# PowerSupply.net
KiCad netlist of a schematic drawn in Altium Designer
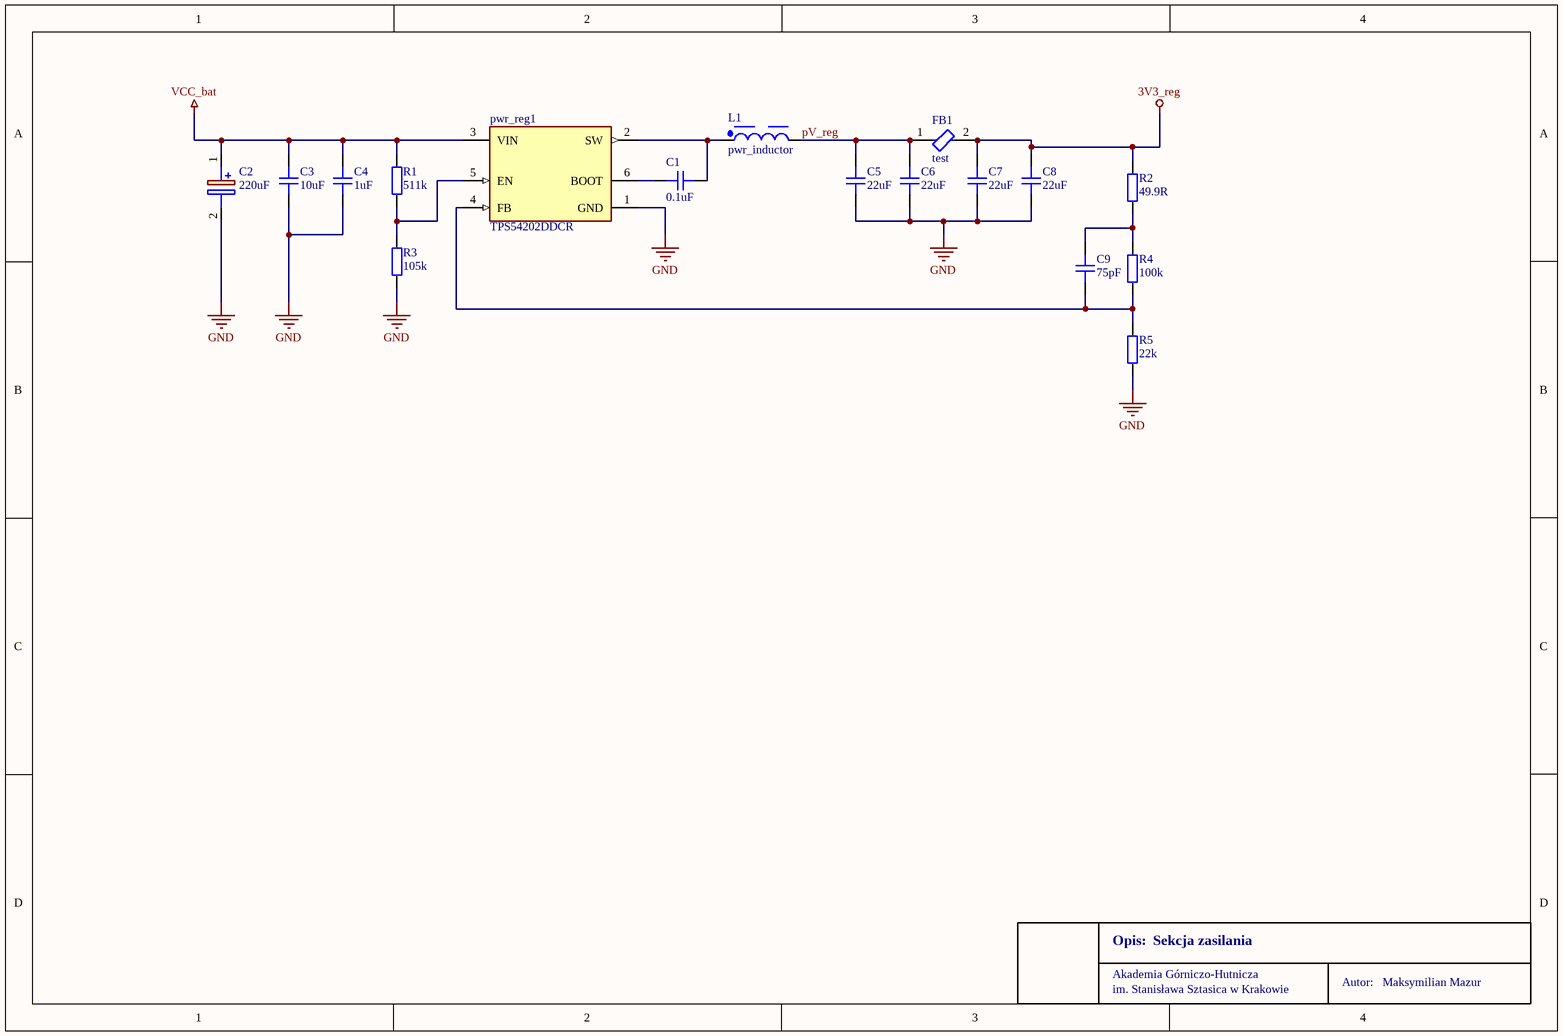
[diagram p0: PowerSupply.SchDoc]

(export (version "E")
  (design (tool "Eeschema 10.0.6"))
  (components
    (comp (ref "C1")
      (value "0.1uF")
      (footprint "CAP_0603")
      (description "Capacitor SMD 0603\r\nX7R\r\nLOW ESR")
      (libsource (lib "Schematic-Lib-PhilsLab") (part "CAP_0603"))
    )
    (comp (ref "C2")
      (value "220uF")
      (footprint "SamacSys:CAPAE660X810N")
      (description "Cap 16V 220uF\r\n\r\nInput current decap")
      (fields (field (name "MANUFACTURER_PART_NUMBER") "SC1C227M6L07KVR"))
      (libsource (lib "*") (part "SC1C227M6L07KVR"))
    )
    (comp (ref "C3")
      (value "10uF")
      (footprint "CAP_1206")
      (description "Capacitor SMD 1206\r\n25V")
      (libsource (lib "Schematic-Lib-PhilsLab") (part "CAP_1206"))
    )
    (comp (ref "C4")
      (value "1uF")
      (footprint "CAP_0603")
      (description "Capacitor SMD 0603\r\n25V")
      (libsource (lib "Schematic-Lib-PhilsLab") (part "CAP_0603"))
    )
    (comp (ref "C5")
      (value "22uF")
      (footprint "CAP_0603")
      (description "Capacitor SMD 0603\r\nX7R\r\nLOW ESR")
      (libsource (lib "Schematic-Lib-PhilsLab") (part "CAP_0603"))
    )
    (comp (ref "C6")
      (value "22uF")
      (footprint "CAP_0603")
      (description "Capacitor SMD 0603\r\nX7R\r\nLOW ESR")
      (libsource (lib "Schematic-Lib-PhilsLab") (part "CAP_0603"))
    )
    (comp (ref "C7")
      (value "22uF")
      (footprint "CAP_0603")
      (description "Capacitor SMD 0603\r\nX7R\r\nLOW ESR")
      (libsource (lib "Schematic-Lib-PhilsLab") (part "CAP_0603"))
    )
    (comp (ref "C8")
      (value "22uF")
      (footprint "CAP_0603")
      (description "Capacitor SMD 0603\r\nX7R\r\nLOW ESR")
      (libsource (lib "Schematic-Lib-PhilsLab") (part "CAP_0603"))
    )
    (comp (ref "C9")
      (value "75pF")
      (footprint "CAP_0603")
      (description "Capacitor SMD 0603")
      (libsource (lib "Schematic-Lib-PhilsLab") (part "CAP_0603"))
    )
    (comp (ref "FB1")
      (value "test")
      (footprint "FP-BLM18-0_15-t0_8-IPC_A")
      (description "Chip Ferrite Bead, 0603\r\n\r\nFor testing purpose")
      (fields (field (name "TOLERANCE") "25%"))
      (libsource (lib "Altium Content Vault") (part "5f30dd21d616792df468990f7003faa"))
    )
    (comp (ref "L1")
      (value "pwr_inductor")
      (footprint "WE-PD_7345")
      (description "15uF, 2.7A  HPI0630-150")
      (fields (field (name "TOLERANCE") "20%"))
      (libsource (lib "Altium Content Vault") (part "Inductor - 2"))
    )
    (comp (ref "pwr_reg1")
      (value "TPS54202DDCR")
      (footprint "FP-DDC0006A-IPC_B")
      (description "IC REG BUCK ADJ 2A TSOT23-6")
      (libsource (lib "Altium Content Vault") (part "35c2d3f1afc239a386b2ba50eead654"))
    )
    (comp (ref "R1")
      (value "511k")
      (footprint "RES_0603")
      (description "Resistor SMD 0603")
      (libsource (lib "Schematic-Lib-PhilsLab") (part "RES_0603"))
    )
    (comp (ref "R2")
      (value "49.9R")
      (footprint "RES_0603")
      (description "Resistor SMD 0603")
      (libsource (lib "Schematic-Lib-PhilsLab") (part "RES_0603"))
    )
    (comp (ref "R3")
      (value "105k")
      (footprint "RES_0603")
      (description "Resistor SMD 0603")
      (libsource (lib "Schematic-Lib-PhilsLab") (part "RES_0603"))
    )
    (comp (ref "R4")
      (value "100k")
      (footprint "RES_0603")
      (description "Resistor SMD 0603\r\nTolerance 1%")
      (libsource (lib "Schematic-Lib-PhilsLab") (part "RES_0603"))
    )
    (comp (ref "R5")
      (value "22k")
      (footprint "RES_0603")
      (description "Resistor SMD 0603\r\nTolerance 1%")
      (libsource (lib "Schematic-Lib-PhilsLab") (part "RES_0603"))
    )
  )
  (nets
    (net (code "1") (name "/pV_reg") (class "Default")
      (node (ref "C5") (pin "2") (pinfunction "2_2") (pintype "passive"))
      (node (ref "C6") (pin "2") (pinfunction "2_2") (pintype "passive"))
      (node (ref "FB1") (pin "1") (pinfunction "1_1") (pintype "passive"))
      (node (ref "L1") (pin "2") (pinfunction "2_2") (pintype "passive"))
    )
    (net (code "2") (name "3V3_reg") (class "Default")
      (node (ref "C7") (pin "2") (pinfunction "2_2") (pintype "passive"))
      (node (ref "C8") (pin "2") (pinfunction "2_2") (pintype "passive"))
      (node (ref "FB1") (pin "2") (pinfunction "2_2") (pintype "passive"))
      (node (ref "R2") (pin "2") (pinfunction "2_2") (pintype "passive"))
    )
    (net (code "3") (name "GND") (class "Default")
      (node (ref "C2") (pin "2") (pinfunction "-_2") (pintype "passive"))
      (node (ref "C3") (pin "1") (pinfunction "1_1") (pintype "passive"))
      (node (ref "C4") (pin "1") (pinfunction "1_1") (pintype "passive"))
      (node (ref "C5") (pin "1") (pinfunction "1_1") (pintype "passive"))
      (node (ref "C6") (pin "1") (pinfunction "1_1") (pintype "passive"))
      (node (ref "C7") (pin "1") (pinfunction "1_1") (pintype "passive"))
      (node (ref "C8") (pin "1") (pinfunction "1_1") (pintype "passive"))
      (node (ref "R3") (pin "1") (pinfunction "1_1") (pintype "passive"))
      (node (ref "R5") (pin "2") (pinfunction "2_2") (pintype "passive"))
      (node (ref "pwr_reg1") (pin "1") (pinfunction "GND_1") (pintype "power_in"))
    )
    (net (code "4") (name "Net-(C9-Pad2)") (class "Default")
      (node (ref "C9") (pin "2") (pinfunction "2_2") (pintype "passive"))
      (node (ref "R2") (pin "1") (pinfunction "1_1") (pintype "passive"))
      (node (ref "R4") (pin "2") (pinfunction "2_2") (pintype "passive"))
    )
    (net (code "5") (name "Net-(pwr_reg1-BOOT)") (class "Default")
      (node (ref "C1") (pin "2") (pinfunction "2_2") (pintype "passive"))
      (node (ref "pwr_reg1") (pin "6") (pinfunction "BOOT_6") (pintype "passive"))
    )
    (net (code "6") (name "Net-(pwr_reg1-EN)") (class "Default")
      (node (ref "R1") (pin "1") (pinfunction "1_1") (pintype "passive"))
      (node (ref "R3") (pin "2") (pinfunction "2_2") (pintype "passive"))
      (node (ref "pwr_reg1") (pin "5") (pinfunction "EN_5") (pintype "input"))
    )
    (net (code "7") (name "Net-(pwr_reg1-FB)") (class "Default")
      (node (ref "C9") (pin "1") (pinfunction "1_1") (pintype "passive"))
      (node (ref "R4") (pin "1") (pinfunction "1_1") (pintype "passive"))
      (node (ref "R5") (pin "1") (pinfunction "1_1") (pintype "passive"))
      (node (ref "pwr_reg1") (pin "4") (pinfunction "FB_4") (pintype "input"))
    )
    (net (code "8") (name "Net-(pwr_reg1-SW)") (class "Default")
      (node (ref "C1") (pin "1") (pinfunction "1_1") (pintype "passive"))
      (node (ref "L1") (pin "1") (pinfunction "1_1") (pintype "passive"))
      (node (ref "pwr_reg1") (pin "2") (pinfunction "SW_2") (pintype "output"))
    )
    (net (code "9") (name "VCC_bat") (class "Default")
      (node (ref "C2") (pin "1") (pinfunction "+_1") (pintype "passive"))
      (node (ref "C3") (pin "2") (pinfunction "2_2") (pintype "passive"))
      (node (ref "C4") (pin "2") (pinfunction "2_2") (pintype "passive"))
      (node (ref "R1") (pin "2") (pinfunction "2_2") (pintype "passive"))
      (node (ref "pwr_reg1") (pin "3") (pinfunction "VIN_3") (pintype "power_in"))
    )
  )
)
